# BTB_CONN.net
KiCad netlist of a schematic drawn in Altium Designer
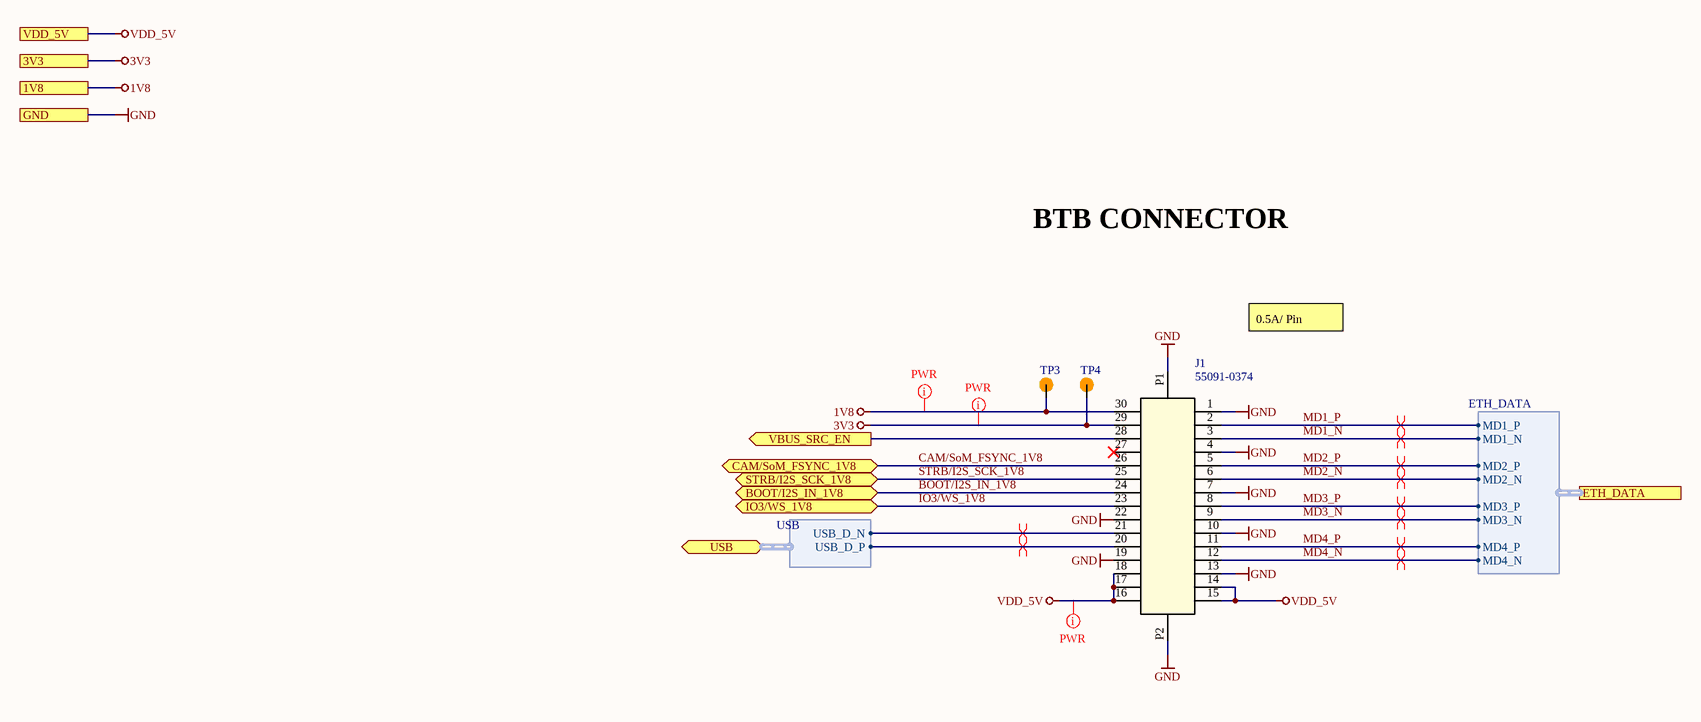
[diagram p0: BTB_CONN.SchDoc]

(export (version "E")
  (design (tool "Eeschema 10.0.6"))
  (components
    (comp (ref "J1")
      (value "55091-0374")
      (footprint "CON_550910374")
      (libsource (lib "Luxonis LLC") (part "55091-0374-Symbol-1"))
    )
    (comp (ref "TP3")
      (value "TP100_200_NS")
      (footprint "TP075_150_NS")
      (libsource (lib "Luxonis LLC") (part "TEST_POINT"))
    )
    (comp (ref "TP4")
      (value "TP100_200_NS")
      (footprint "TP075_150_NS")
      (libsource (lib "Luxonis LLC") (part "TEST_POINT"))
    )
  )
  (nets
    (net (code "3") (name "/BOOT{slash}I2S_IN_1V8") (class "Default")
      (node (ref "J1") (pin "24") (pinfunction "24_24") (pintype "passive"))
    )
    (net (code "4") (name "/CAM{slash}SoM_FSYNC_1V8") (class "Default")
      (node (ref "J1") (pin "26") (pinfunction "26_26") (pintype "passive"))
    )
    (net (code "5") (name "/IO3{slash}WS_1V8") (class "Default")
      (node (ref "J1") (pin "23") (pinfunction "23_23") (pintype "passive"))
    )
    (net (code "6") (name "/MD1_N") (class "Default")
      (node (ref "J1") (pin "3") (pinfunction "3_3") (pintype "passive"))
    )
    (net (code "7") (name "/MD1_P") (class "Default")
      (node (ref "J1") (pin "2") (pinfunction "2_2") (pintype "passive"))
    )
    (net (code "8") (name "/MD2_N") (class "Default")
      (node (ref "J1") (pin "6") (pinfunction "6_6") (pintype "passive"))
    )
    (net (code "9") (name "/MD2_P") (class "Default")
      (node (ref "J1") (pin "5") (pinfunction "5_5") (pintype "passive"))
    )
    (net (code "10") (name "/MD3_N") (class "Default")
      (node (ref "J1") (pin "9") (pinfunction "9_9") (pintype "passive"))
    )
    (net (code "11") (name "/MD3_P") (class "Default")
      (node (ref "J1") (pin "8") (pinfunction "8_8") (pintype "passive"))
    )
    (net (code "12") (name "/MD4_N") (class "Default")
      (node (ref "J1") (pin "12") (pinfunction "12_12") (pintype "passive"))
    )
    (net (code "13") (name "/MD4_P") (class "Default")
      (node (ref "J1") (pin "11") (pinfunction "11_11") (pintype "passive"))
    )
    (net (code "14") (name "/STRB{slash}I2S_SCK_1V8") (class "Default")
      (node (ref "J1") (pin "25") (pinfunction "25_25") (pintype "passive"))
    )
    (net (code "15") (name "/USB_D_N") (class "Default")
      (node (ref "J1") (pin "21") (pinfunction "21_21") (pintype "passive"))
    )
    (net (code "16") (name "/USB_D_P") (class "Default")
      (node (ref "J1") (pin "20") (pinfunction "20_20") (pintype "passive"))
    )
    (net (code "17") (name "/VBUS_SRC_EN") (class "Default")
      (node (ref "J1") (pin "28") (pinfunction "28_28") (pintype "passive"))
    )
    (net (code "20") (name "1V8") (class "Default")
      (node (ref "J1") (pin "30") (pinfunction "30_30") (pintype "passive"))
      (node (ref "TP3") (pin "1") (pintype "passive"))
    )
    (net (code "21") (name "3V3") (class "Default")
      (node (ref "J1") (pin "29") (pinfunction "29_29") (pintype "passive"))
      (node (ref "TP4") (pin "1") (pintype "passive"))
    )
    (net (code "22") (name "GND") (class "Default")
      (node (ref "J1") (pin "1") (pinfunction "1_1") (pintype "passive"))
      (node (ref "J1") (pin "10") (pinfunction "10_10") (pintype "passive"))
      (node (ref "J1") (pin "13") (pinfunction "13_13") (pintype "passive"))
      (node (ref "J1") (pin "19") (pinfunction "19_19") (pintype "passive"))
      (node (ref "J1") (pin "22") (pinfunction "22_22") (pintype "passive"))
      (node (ref "J1") (pin "4") (pinfunction "4_4") (pintype "passive"))
      (node (ref "J1") (pin "7") (pinfunction "7_7") (pintype "passive"))
      (node (ref "J1") (pin "P1") (pinfunction "P1_P1") (pintype "passive"))
      (node (ref "J1") (pin "P2") (pinfunction "P2_P2") (pintype "passive"))
    )
    (net (code "23") (name "VDD_5V") (class "Default")
      (node (ref "J1") (pin "14") (pinfunction "14_14") (pintype "passive"))
      (node (ref "J1") (pin "15") (pinfunction "15_15") (pintype "passive"))
      (node (ref "J1") (pin "16") (pinfunction "16_16") (pintype "passive"))
      (node (ref "J1") (pin "17") (pinfunction "17_17") (pintype "passive"))
      (node (ref "J1") (pin "18") (pinfunction "18_18") (pintype "passive"))
    )
    (net (code "24") (name "unconnected-(J1-Pad27)") (class "Default")
      (node (ref "J1") (pin "27") (pinfunction "27_27") (pintype "passive+no_connect"))
    )
  )
)
